# Stepper_driver_group.net
KiCad netlist of a schematic drawn in Altium Designer
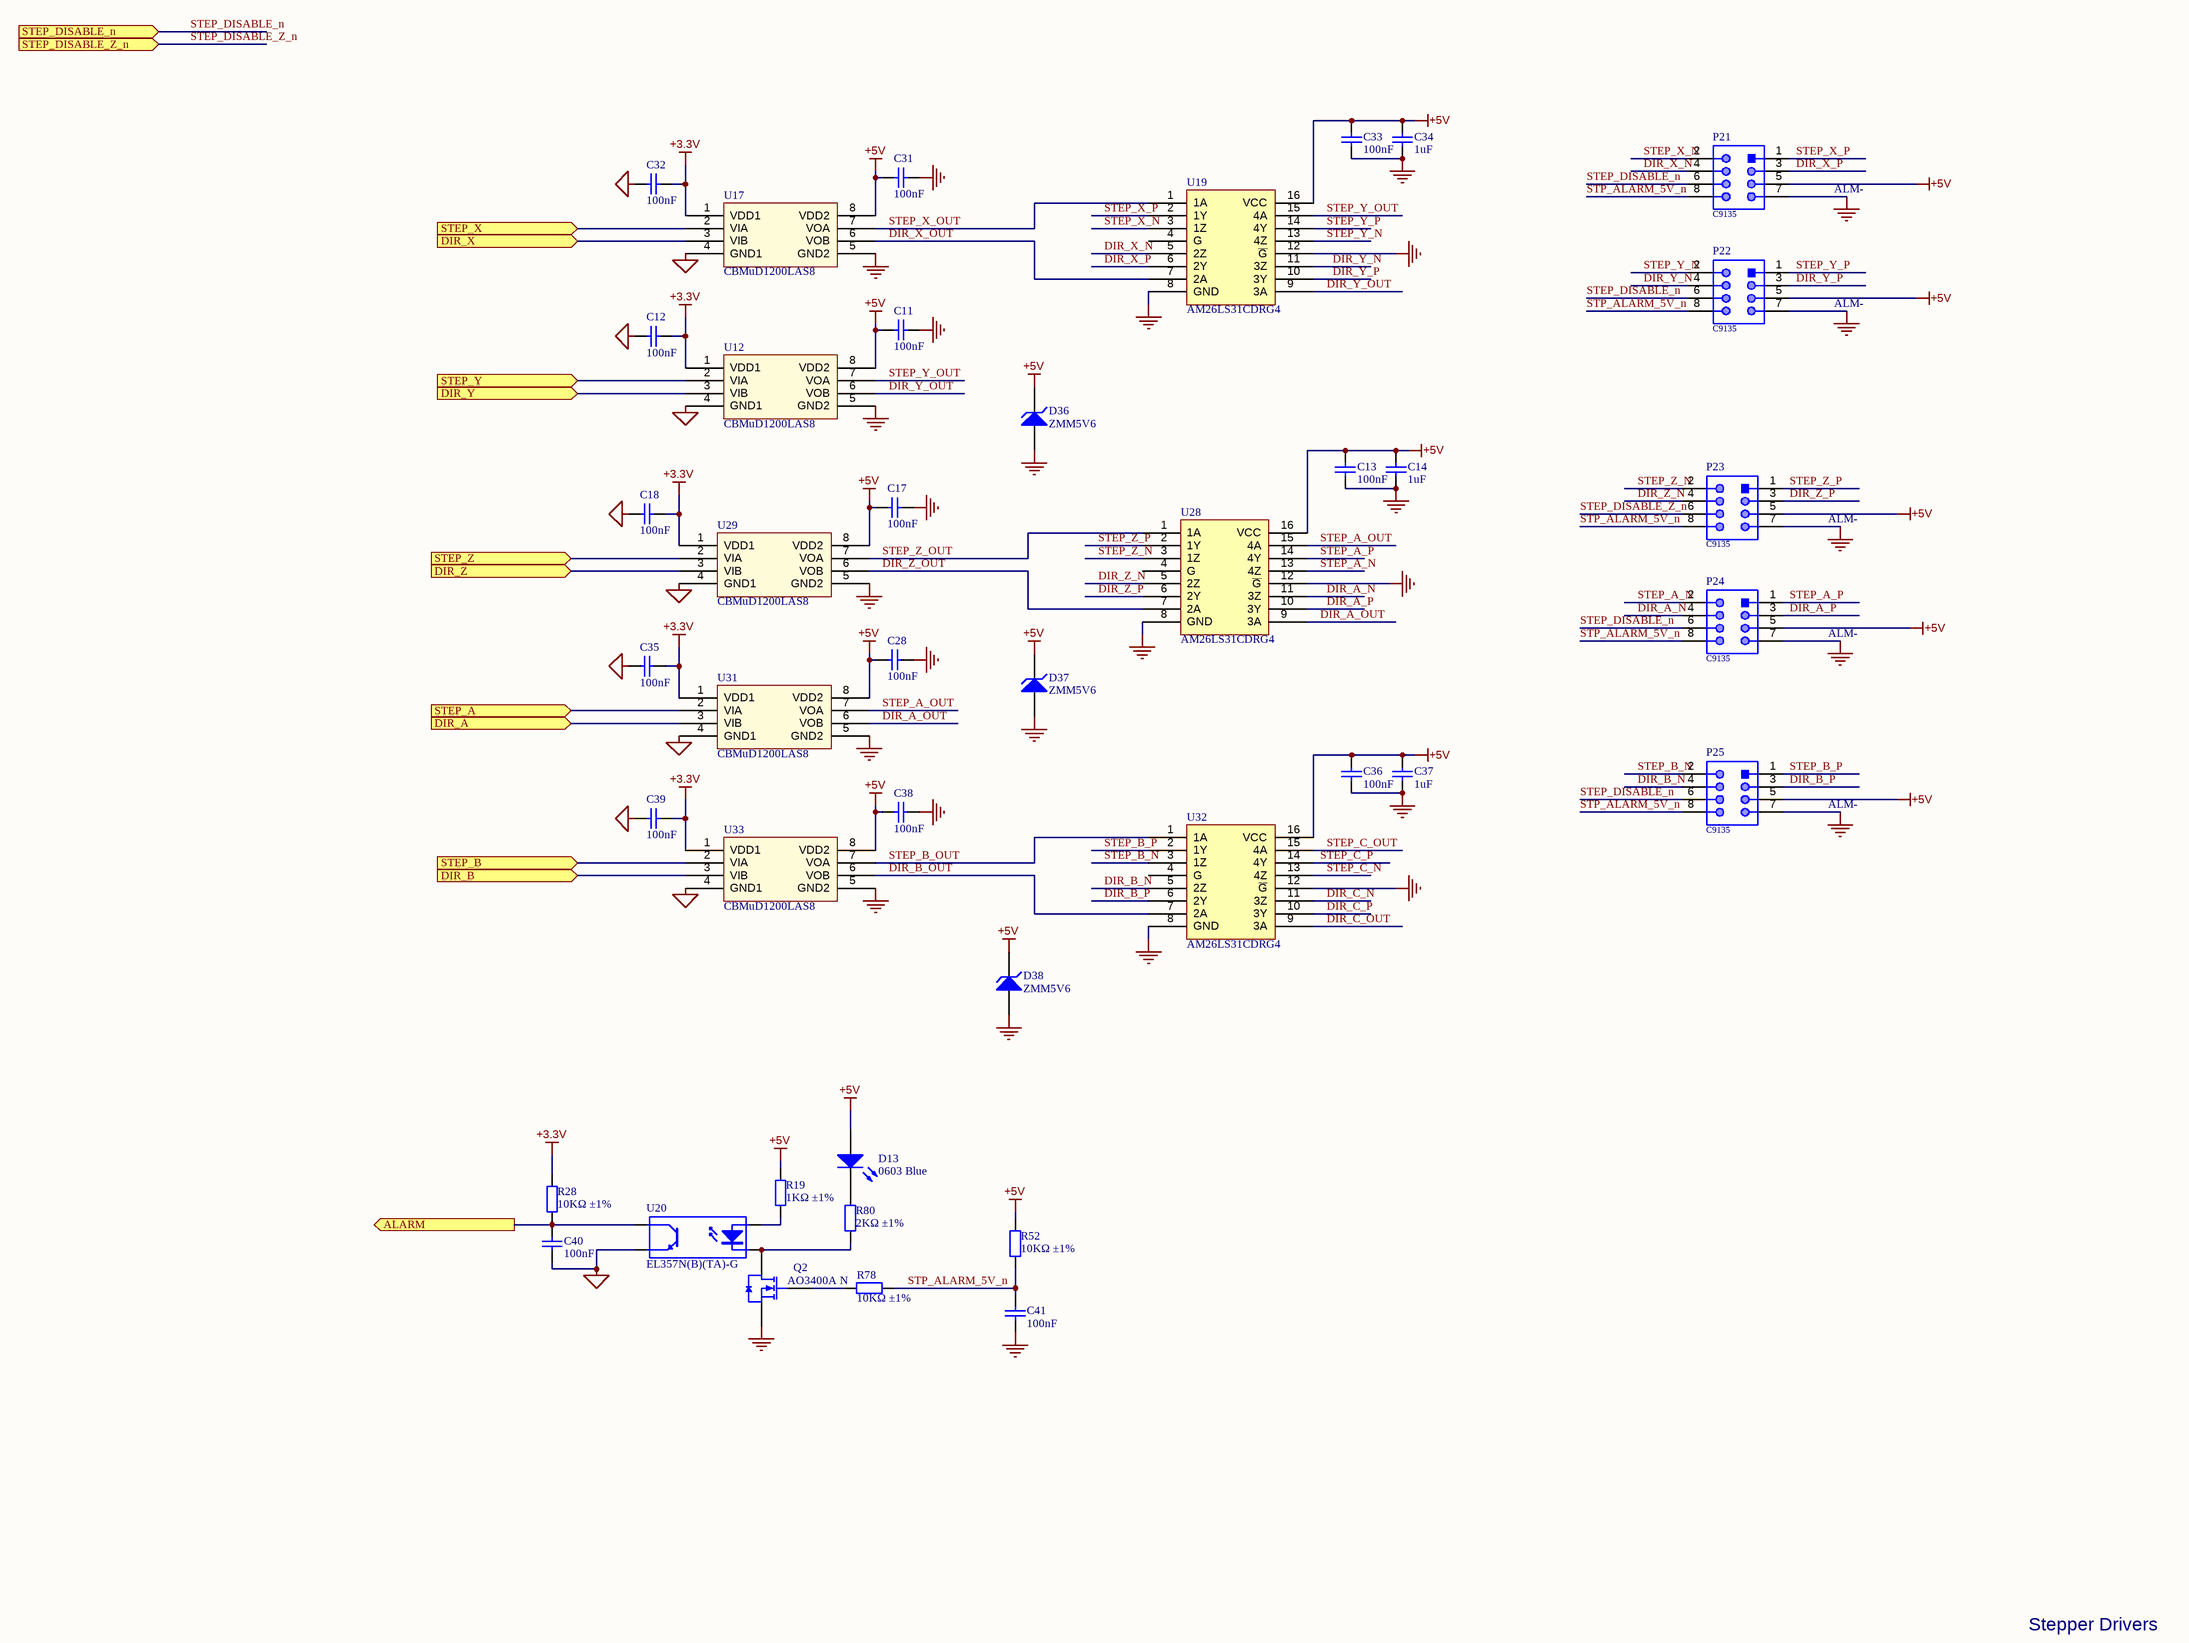
[diagram p0: Stepper_driver_group.SchDoc]

(export (version "E")
  (design (tool "Eeschema 10.0.6"))
  (components
    (comp (ref "C11")
      (value "100nF")
      (footprint "0603_C")
      (description "Chip capacitors")
      (fields (field (name "MANUFACTURER") "YAGEO") (field (name "PARTNUMBER") "CC0603KRX7R9BB104"))
      (libsource (lib "Cap") (part "0603 100nF (104) 10% 50V"))
    )
    (comp (ref "C12")
      (value "100nF")
      (footprint "0603_C")
      (description "Chip capacitors")
      (fields (field (name "MANUFACTURER") "YAGEO") (field (name "PARTNUMBER") "CC0603KRX7R9BB104"))
      (libsource (lib "Cap") (part "0603 100nF (104) 10% 50V"))
    )
    (comp (ref "C13")
      (value "100nF")
      (footprint "0603_C")
      (description "Chip capacitors")
      (fields (field (name "MANUFACTURER") "YAGEO") (field (name "PARTNUMBER") "CC0603KRX7R9BB104"))
      (libsource (lib "Cap") (part "0603 100nF (104) 10% 50V"))
    )
    (comp (ref "C14")
      (value "1uF")
      (footprint "0603_C")
      (description "Chip capacitors")
      (fields
        (field (name "MANUFACTURER") "Samsung Electro-Mechanics")
        (field (name "PARTNUMBER") "CL10A105KB8NNNC")
      )
      (libsource (lib "Cap") (part "0603 1uF (105) 10% 50V"))
    )
    (comp (ref "C17")
      (value "100nF")
      (footprint "0603_C")
      (description "Chip capacitors")
      (fields (field (name "MANUFACTURER") "YAGEO") (field (name "PARTNUMBER") "CC0603KRX7R9BB104"))
      (libsource (lib "Cap") (part "0603 100nF (104) 10% 50V"))
    )
    (comp (ref "C18")
      (value "100nF")
      (footprint "0603_C")
      (description "Chip capacitors")
      (fields (field (name "MANUFACTURER") "YAGEO") (field (name "PARTNUMBER") "CC0603KRX7R9BB104"))
      (libsource (lib "Cap") (part "0603 100nF (104) 10% 50V"))
    )
    (comp (ref "C28")
      (value "100nF")
      (footprint "0603_C")
      (description "Chip capacitors")
      (fields (field (name "MANUFACTURER") "YAGEO") (field (name "PARTNUMBER") "CC0603KRX7R9BB104"))
      (libsource (lib "Cap") (part "0603 100nF (104) 10% 50V"))
    )
    (comp (ref "C31")
      (value "100nF")
      (footprint "0603_C")
      (description "Chip capacitors")
      (fields (field (name "MANUFACTURER") "YAGEO") (field (name "PARTNUMBER") "CC0603KRX7R9BB104"))
      (libsource (lib "Cap") (part "0603 100nF (104) 10% 50V"))
    )
    (comp (ref "C32")
      (value "100nF")
      (footprint "0603_C")
      (description "Chip capacitors")
      (fields (field (name "MANUFACTURER") "YAGEO") (field (name "PARTNUMBER") "CC0603KRX7R9BB104"))
      (libsource (lib "Cap") (part "0603 100nF (104) 10% 50V"))
    )
    (comp (ref "C33")
      (value "100nF")
      (footprint "0603_C")
      (description "Chip capacitors")
      (fields (field (name "MANUFACTURER") "YAGEO") (field (name "PARTNUMBER") "CC0603KRX7R9BB104"))
      (libsource (lib "Cap") (part "0603 100nF (104) 10% 50V"))
    )
    (comp (ref "C34")
      (value "1uF")
      (footprint "0603_C")
      (description "Chip capacitors")
      (fields
        (field (name "MANUFACTURER") "Samsung Electro-Mechanics")
        (field (name "PARTNUMBER") "CL10A105KB8NNNC")
      )
      (libsource (lib "Cap") (part "0603 1uF (105) 10% 50V"))
    )
    (comp (ref "C35")
      (value "100nF")
      (footprint "0603_C")
      (description "Chip capacitors")
      (fields (field (name "MANUFACTURER") "YAGEO") (field (name "PARTNUMBER") "CC0603KRX7R9BB104"))
      (libsource (lib "Cap") (part "0603 100nF (104) 10% 50V"))
    )
    (comp (ref "C36")
      (value "100nF")
      (footprint "0603_C")
      (description "Chip capacitors")
      (fields (field (name "MANUFACTURER") "YAGEO") (field (name "PARTNUMBER") "CC0603KRX7R9BB104"))
      (libsource (lib "Cap") (part "0603 100nF (104) 10% 50V"))
    )
    (comp (ref "C37")
      (value "1uF")
      (footprint "0603_C")
      (description "Chip capacitors")
      (fields
        (field (name "MANUFACTURER") "Samsung Electro-Mechanics")
        (field (name "PARTNUMBER") "CL10A105KB8NNNC")
      )
      (libsource (lib "Cap") (part "0603 1uF (105) 10% 50V"))
    )
    (comp (ref "C38")
      (value "100nF")
      (footprint "0603_C")
      (description "Chip capacitors")
      (fields (field (name "MANUFACTURER") "YAGEO") (field (name "PARTNUMBER") "CC0603KRX7R9BB104"))
      (libsource (lib "Cap") (part "0603 100nF (104) 10% 50V"))
    )
    (comp (ref "C39")
      (value "100nF")
      (footprint "0603_C")
      (description "Chip capacitors")
      (fields (field (name "MANUFACTURER") "YAGEO") (field (name "PARTNUMBER") "CC0603KRX7R9BB104"))
      (libsource (lib "Cap") (part "0603 100nF (104) 10% 50V"))
    )
    (comp (ref "C40")
      (value "100nF")
      (footprint "0603_C")
      (description "Chip capacitors")
      (fields (field (name "MANUFACTURER") "YAGEO") (field (name "PARTNUMBER") "CC0603KRX7R9BB104"))
      (libsource (lib "Cap") (part "0603 100nF (104) 10% 50V"))
    )
    (comp (ref "C41")
      (value "100nF")
      (footprint "0603_C")
      (description "Chip capacitors")
      (fields (field (name "MANUFACTURER") "YAGEO") (field (name "PARTNUMBER") "CC0603KRX7R9BB104"))
      (libsource (lib "Cap") (part "0603 100nF (104) 10% 50V"))
    )
    (comp (ref "D13")
      (value "0603 Blue")
      (footprint "0603_LED_S1")
      (description "LED")
      (libsource (lib "LED") (part "0603 LED Blue"))
    )
    (comp (ref "D36")
      (value "ZMM5V6")
      (footprint "LL-34")
      (description "500mW - 0.1uA @ 1V 5.6V LL-34 Zener Diodes ROHS")
      (libsource (lib "Zener") (part "LL-34 ZMM5V6"))
    )
    (comp (ref "D37")
      (value "ZMM5V6")
      (footprint "LL-34")
      (description "500mW - 0.1uA @ 1V 5.6V LL-34 Zener Diodes ROHS")
      (libsource (lib "Zener") (part "LL-34 ZMM5V6"))
    )
    (comp (ref "D38")
      (value "ZMM5V6")
      (footprint "LL-34")
      (description "500mW - 0.1uA @ 1V 5.6V LL-34 Zener Diodes ROHS")
      (libsource (lib "Zener") (part "LL-34 ZMM5V6"))
    )
    (comp (ref "P21")
      (value "C9135")
      (footprint "61200821621")
      (description "Male Box Header WR-BHD, THT, Vertical, pitch 2.54 mm, 8 pins")
      (fields (field (name "MANUFACTURER") "Wurth Elektronik") (field (name "PUBLISHER") "WurthElektronik"))
      (libsource (lib "PrintNC_GRBLHAL_Breakout") (part "WE-CN-2P-M-R8"))
    )
    (comp (ref "P22")
      (value "C9135")
      (footprint "61200821621")
      (description "Male Box Header WR-BHD, THT, Vertical, pitch 2.54 mm, 8 pins")
      (fields (field (name "MANUFACTURER") "Wurth Elektronik") (field (name "PUBLISHER") "WurthElektronik"))
      (libsource (lib "PrintNC_GRBLHAL_Breakout") (part "WE-CN-2P-M-R8"))
    )
    (comp (ref "P23")
      (value "C9135")
      (footprint "61200821621")
      (description "Male Box Header WR-BHD, THT, Vertical, pitch 2.54 mm, 8 pins")
      (fields (field (name "MANUFACTURER") "Wurth Elektronik") (field (name "PUBLISHER") "WurthElektronik"))
      (libsource (lib "PrintNC_GRBLHAL_Breakout") (part "WE-CN-2P-M-R8"))
    )
    (comp (ref "P24")
      (value "C9135")
      (footprint "61200821621")
      (description "Male Box Header WR-BHD, THT, Vertical, pitch 2.54 mm, 8 pins")
      (fields (field (name "MANUFACTURER") "Wurth Elektronik") (field (name "PUBLISHER") "WurthElektronik"))
      (libsource (lib "PrintNC_GRBLHAL_Breakout") (part "WE-CN-2P-M-R8"))
    )
    (comp (ref "P25")
      (value "C9135")
      (footprint "61200821621")
      (description "Male Box Header WR-BHD, THT, Vertical, pitch 2.54 mm, 8 pins")
      (fields (field (name "MANUFACTURER") "Wurth Elektronik") (field (name "PUBLISHER") "WurthElektronik"))
      (libsource (lib "PrintNC_GRBLHAL_Breakout") (part "WE-CN-2P-M-R8"))
    )
    (comp (ref "Q2")
      (value "AO3400A N")
      (footprint "SOT-23-3L")
      (description "MOS(场效应管)")
      (libsource (lib "MOS") (part "AO3400A N道沟 X0YV1T SOT-23"))
    )
    (comp (ref "R19")
      (value "1KΩ ±1%")
      (footprint "0603_R")
      (description "Chip resistor")
      (fields (field (name "MANUFACTURER") "Uniroyal Elec") (field (name "PARTNUMBER") "0603WAF1001T5E"))
      (libsource (lib "RES") (part "0603 1K (1001) 1%"))
    )
    (comp (ref "R28")
      (value "10KΩ ±1%")
      (footprint "0603_R")
      (description "Chip resistor")
      (fields (field (name "MANUFACTURER") "Uniroyal Elec") (field (name "PARTNUMBER") "0603WAF1002T5E"))
      (libsource (lib "") (part "0603 10K (1002) 1%_1"))
    )
    (comp (ref "R52")
      (value "10KΩ ±1%")
      (footprint "0603_R")
      (description "Chip resistor")
      (fields (field (name "MANUFACTURER") "Uniroyal Elec") (field (name "PARTNUMBER") "0603WAF1002T5E"))
      (libsource (lib "") (part "0603 10K (1002) 1%_2"))
    )
    (comp (ref "R78")
      (value "10KΩ ±1%")
      (footprint "0603_R")
      (description "Chip resistor")
      (fields (field (name "MANUFACTURER") "Uniroyal Elec") (field (name "PARTNUMBER") "0603WAF1002T5E"))
      (libsource (lib "RES") (part "0603 10K (1002) 1%"))
    )
    (comp (ref "R80")
      (value "2KΩ ±1%")
      (footprint "0603_R")
      (description "Chip resistor")
      (fields (field (name "MANUFACTURER") "Uniroyal Elec") (field (name "PARTNUMBER") "0603WAF2001T5E"))
      (libsource (lib "RES") (part "0603 2K (2001) 1%"))
    )
    (comp (ref "U12")
      (value "CBMuD1200LAS8")
      (footprint "SOIC-8_150mil")
      (description "Dual Channel Isolator")
      (libsource (lib "IC") (part "CBMuD1200LAS8"))
    )
    (comp (ref "U17")
      (value "CBMuD1200LAS8")
      (footprint "SOIC-8_150mil")
      (description "Dual Channel Isolator")
      (libsource (lib "IC") (part "CBMuD1200LAS8"))
    )
    (comp (ref "U19")
      (value "AM26LS31CDRG4")
      (footprint "SOIC-16_150mil")
      (description "4/0 Driver - RS422, RS485 16-SOIC")
      (libsource (lib "IC") (part "AM26LS31CDRG4_[C6179]"))
    )
    (comp (ref "U20")
      (value "EL357N(B)(TA)-G")
      (footprint "SOP-4_P2.54")
      (description "OPTOISOLATOR 3.75KV TRANS 4-SOP")
      (libsource (lib "PrintNC_GRBLHAL_Breakout") (part "EL357N(B)(TA)-G_[C6649]"))
    )
    (comp (ref "U28")
      (value "AM26LS31CDRG4")
      (footprint "SOIC-16_150mil")
      (description "4/0 Driver - RS422, RS485 16-SOIC")
      (libsource (lib "IC") (part "AM26LS31CDRG4_[C6179]"))
    )
    (comp (ref "U29")
      (value "CBMuD1200LAS8")
      (footprint "SOIC-8_150mil")
      (description "Dual Channel Isolator")
      (libsource (lib "IC") (part "CBMuD1200LAS8"))
    )
    (comp (ref "U31")
      (value "CBMuD1200LAS8")
      (footprint "SOIC-8_150mil")
      (description "Dual Channel Isolator")
      (libsource (lib "IC") (part "CBMuD1200LAS8"))
    )
    (comp (ref "U32")
      (value "AM26LS31CDRG4")
      (footprint "SOIC-16_150mil")
      (description "4/0 Driver - RS422, RS485 16-SOIC")
      (libsource (lib "IC") (part "AM26LS31CDRG4_[C6179]"))
    )
    (comp (ref "U33")
      (value "CBMuD1200LAS8")
      (footprint "SOIC-8_150mil")
      (description "Dual Channel Isolator")
      (libsource (lib "IC") (part "CBMuD1200LAS8"))
    )
  )
  (nets
    (net (code "1") (name "+3.3V") (class "Default")
      (node (ref "C12") (pin "1") (pinfunction "1_1") (pintype "passive"))
      (node (ref "C18") (pin "1") (pinfunction "1_1") (pintype "passive"))
      (node (ref "C32") (pin "1") (pinfunction "1_1") (pintype "passive"))
      (node (ref "C35") (pin "1") (pinfunction "1_1") (pintype "passive"))
      (node (ref "C39") (pin "1") (pinfunction "1_1") (pintype "passive"))
      (node (ref "R28") (pin "2") (pinfunction "2_2") (pintype "passive"))
      (node (ref "U12") (pin "1") (pinfunction "VDD1_1") (pintype "passive"))
      (node (ref "U17") (pin "1") (pinfunction "VDD1_1") (pintype "passive"))
      (node (ref "U29") (pin "1") (pinfunction "VDD1_1") (pintype "passive"))
      (node (ref "U31") (pin "1") (pinfunction "VDD1_1") (pintype "passive"))
      (node (ref "U33") (pin "1") (pinfunction "VDD1_1") (pintype "passive"))
    )
    (net (code "2") (name "+5V") (class "Default")
      (node (ref "C11") (pin "2") (pinfunction "2_2") (pintype "passive"))
      (node (ref "C13") (pin "1") (pinfunction "1_1") (pintype "passive"))
      (node (ref "C14") (pin "1") (pinfunction "1_1") (pintype "passive"))
      (node (ref "C17") (pin "2") (pinfunction "2_2") (pintype "passive"))
      (node (ref "C28") (pin "2") (pinfunction "2_2") (pintype "passive"))
      (node (ref "C31") (pin "2") (pinfunction "2_2") (pintype "passive"))
      (node (ref "C33") (pin "1") (pinfunction "1_1") (pintype "passive"))
      (node (ref "C34") (pin "1") (pinfunction "1_1") (pintype "passive"))
      (node (ref "C36") (pin "1") (pinfunction "1_1") (pintype "passive"))
      (node (ref "C37") (pin "1") (pinfunction "1_1") (pintype "passive"))
      (node (ref "C38") (pin "2") (pinfunction "2_2") (pintype "passive"))
      (node (ref "D13") (pin "A") (pinfunction "A_A") (pintype "passive"))
      (node (ref "D36") (pin "2") (pinfunction "K_2") (pintype "passive"))
      (node (ref "D37") (pin "2") (pinfunction "K_2") (pintype "passive"))
      (node (ref "D38") (pin "2") (pinfunction "K_2") (pintype "passive"))
      (node (ref "P21") (pin "5") (pinfunction "5_5") (pintype "passive"))
      (node (ref "P22") (pin "5") (pinfunction "5_5") (pintype "passive"))
      (node (ref "P23") (pin "5") (pinfunction "5_5") (pintype "passive"))
      (node (ref "P24") (pin "5") (pinfunction "5_5") (pintype "passive"))
      (node (ref "P25") (pin "5") (pinfunction "5_5") (pintype "passive"))
      (node (ref "R19") (pin "1") (pinfunction "1_1") (pintype "passive"))
      (node (ref "R52") (pin "2") (pinfunction "2_2") (pintype "passive"))
      (node (ref "U12") (pin "8") (pinfunction "VDD2_8") (pintype "passive"))
      (node (ref "U17") (pin "8") (pinfunction "VDD2_8") (pintype "passive"))
      (node (ref "U19") (pin "16") (pinfunction "VCC_16") (pintype "passive"))
      (node (ref "U28") (pin "16") (pinfunction "VCC_16") (pintype "passive"))
      (node (ref "U29") (pin "8") (pinfunction "VDD2_8") (pintype "passive"))
      (node (ref "U31") (pin "8") (pinfunction "VDD2_8") (pintype "passive"))
      (node (ref "U32") (pin "16") (pinfunction "VCC_16") (pintype "passive"))
      (node (ref "U33") (pin "8") (pinfunction "VDD2_8") (pintype "passive"))
    )
    (net (code "3") (name "/ALARM") (class "Default")
      (node (ref "C40") (pin "2") (pinfunction "2_2") (pintype "passive"))
      (node (ref "R28") (pin "1") (pinfunction "1_1") (pintype "passive"))
      (node (ref "U20") (pin "4") (pinfunction "C_4") (pintype "passive"))
    )
    (net (code "4") (name "/DIR_A") (class "Default")
      (node (ref "U31") (pin "3") (pinfunction "VIB_3") (pintype "passive"))
    )
    (net (code "5") (name "/DIR_A_N") (class "Default")
      (node (ref "P24") (pin "4") (pinfunction "4_4") (pintype "passive"))
      (node (ref "U28") (pin "11") (pinfunction "3Z_11") (pintype "passive"))
    )
    (net (code "6") (name "/DIR_A_OUT") (class "Default")
      (node (ref "U28") (pin "9") (pinfunction "3A_9") (pintype "passive"))
      (node (ref "U31") (pin "6") (pinfunction "VOB_6") (pintype "passive"))
    )
    (net (code "7") (name "/DIR_A_P") (class "Default")
      (node (ref "P24") (pin "3") (pinfunction "3_3") (pintype "passive"))
      (node (ref "U28") (pin "10") (pinfunction "3Y_10") (pintype "passive"))
    )
    (net (code "8") (name "/DIR_B") (class "Default")
      (node (ref "U33") (pin "3") (pinfunction "VIB_3") (pintype "passive"))
    )
    (net (code "9") (name "/DIR_B_N") (class "Default")
      (node (ref "P25") (pin "4") (pinfunction "4_4") (pintype "passive"))
      (node (ref "U32") (pin "5") (pinfunction "2Z_5") (pintype "passive"))
    )
    (net (code "10") (name "/DIR_B_OUT") (class "Default")
      (node (ref "U32") (pin "7") (pinfunction "2A_7") (pintype "passive"))
      (node (ref "U33") (pin "6") (pinfunction "VOB_6") (pintype "passive"))
    )
    (net (code "11") (name "/DIR_B_P") (class "Default")
      (node (ref "P25") (pin "3") (pinfunction "3_3") (pintype "passive"))
      (node (ref "U32") (pin "6") (pinfunction "2Y_6") (pintype "passive"))
    )
    (net (code "12") (name "/DIR_C_N") (class "Default")
      (node (ref "U32") (pin "11") (pinfunction "3Z_11") (pintype "passive"))
    )
    (net (code "13") (name "/DIR_C_OUT") (class "Default")
      (node (ref "U32") (pin "9") (pinfunction "3A_9") (pintype "passive"))
    )
    (net (code "14") (name "/DIR_C_P") (class "Default")
      (node (ref "U32") (pin "10") (pinfunction "3Y_10") (pintype "passive"))
    )
    (net (code "15") (name "/DIR_X") (class "Default")
      (node (ref "U17") (pin "3") (pinfunction "VIB_3") (pintype "passive"))
    )
    (net (code "16") (name "/DIR_X_N") (class "Default")
      (node (ref "P21") (pin "4") (pinfunction "4_4") (pintype "passive"))
      (node (ref "U19") (pin "5") (pinfunction "2Z_5") (pintype "passive"))
    )
    (net (code "17") (name "/DIR_X_OUT") (class "Default")
      (node (ref "U17") (pin "6") (pinfunction "VOB_6") (pintype "passive"))
      (node (ref "U19") (pin "7") (pinfunction "2A_7") (pintype "passive"))
    )
    (net (code "18") (name "/DIR_X_P") (class "Default")
      (node (ref "P21") (pin "3") (pinfunction "3_3") (pintype "passive"))
      (node (ref "U19") (pin "6") (pinfunction "2Y_6") (pintype "passive"))
    )
    (net (code "19") (name "/DIR_Y") (class "Default")
      (node (ref "U12") (pin "3") (pinfunction "VIB_3") (pintype "passive"))
    )
    (net (code "20") (name "/DIR_Y_N") (class "Default")
      (node (ref "P22") (pin "4") (pinfunction "4_4") (pintype "passive"))
      (node (ref "U19") (pin "11") (pinfunction "3Z_11") (pintype "passive"))
    )
    (net (code "21") (name "/DIR_Y_OUT") (class "Default")
      (node (ref "U12") (pin "6") (pinfunction "VOB_6") (pintype "passive"))
      (node (ref "U19") (pin "9") (pinfunction "3A_9") (pintype "passive"))
    )
    (net (code "22") (name "/DIR_Y_P") (class "Default")
      (node (ref "P22") (pin "3") (pinfunction "3_3") (pintype "passive"))
      (node (ref "U19") (pin "10") (pinfunction "3Y_10") (pintype "passive"))
    )
    (net (code "23") (name "/DIR_Z") (class "Default")
      (node (ref "U29") (pin "3") (pinfunction "VIB_3") (pintype "passive"))
    )
    (net (code "24") (name "/DIR_Z_N") (class "Default")
      (node (ref "P23") (pin "4") (pinfunction "4_4") (pintype "passive"))
      (node (ref "U28") (pin "5") (pinfunction "2Z_5") (pintype "passive"))
    )
    (net (code "25") (name "/DIR_Z_OUT") (class "Default")
      (node (ref "U28") (pin "7") (pinfunction "2A_7") (pintype "passive"))
      (node (ref "U29") (pin "6") (pinfunction "VOB_6") (pintype "passive"))
    )
    (net (code "26") (name "/DIR_Z_P") (class "Default")
      (node (ref "P23") (pin "3") (pinfunction "3_3") (pintype "passive"))
      (node (ref "U28") (pin "6") (pinfunction "2Y_6") (pintype "passive"))
    )
    (net (code "27") (name "/STEP_A") (class "Default")
      (node (ref "U31") (pin "2") (pinfunction "VIA_2") (pintype "passive"))
    )
    (net (code "28") (name "/STEP_A_N") (class "Default")
      (node (ref "P24") (pin "2") (pinfunction "2_2") (pintype "passive"))
      (node (ref "U28") (pin "13") (pinfunction "4Z_13") (pintype "passive"))
    )
    (net (code "29") (name "/STEP_A_OUT") (class "Default")
      (node (ref "U28") (pin "15") (pinfunction "4A_15") (pintype "passive"))
      (node (ref "U31") (pin "7") (pinfunction "VOA_7") (pintype "passive"))
    )
    (net (code "30") (name "/STEP_A_P") (class "Default")
      (node (ref "P24") (pin "1") (pinfunction "1_1") (pintype "passive"))
      (node (ref "U28") (pin "14") (pinfunction "4Y_14") (pintype "passive"))
    )
    (net (code "31") (name "/STEP_B") (class "Default")
      (node (ref "U33") (pin "2") (pinfunction "VIA_2") (pintype "passive"))
    )
    (net (code "32") (name "/STEP_B_N") (class "Default")
      (node (ref "P25") (pin "2") (pinfunction "2_2") (pintype "passive"))
      (node (ref "U32") (pin "3") (pinfunction "1Z_3") (pintype "passive"))
    )
    (net (code "33") (name "/STEP_B_OUT") (class "Default")
      (node (ref "U32") (pin "1") (pinfunction "1A_1") (pintype "passive"))
      (node (ref "U33") (pin "7") (pinfunction "VOA_7") (pintype "passive"))
    )
    (net (code "34") (name "/STEP_B_P") (class "Default")
      (node (ref "P25") (pin "1") (pinfunction "1_1") (pintype "passive"))
      (node (ref "U32") (pin "2") (pinfunction "1Y_2") (pintype "passive"))
    )
    (net (code "35") (name "/STEP_C_N") (class "Default")
      (node (ref "U32") (pin "13") (pinfunction "4Z_13") (pintype "passive"))
    )
    (net (code "36") (name "/STEP_C_OUT") (class "Default")
      (node (ref "U32") (pin "15") (pinfunction "4A_15") (pintype "passive"))
    )
    (net (code "37") (name "/STEP_C_P") (class "Default")
      (node (ref "U32") (pin "14") (pinfunction "4Y_14") (pintype "passive"))
    )
    (net (code "38") (name "/STEP_DISABLE_Z_n") (class "Default")
      (node (ref "P23") (pin "6") (pinfunction "6_6") (pintype "passive"))
    )
    (net (code "39") (name "/STEP_DISABLE_n") (class "Default")
      (node (ref "P21") (pin "6") (pinfunction "6_6") (pintype "passive"))
      (node (ref "P22") (pin "6") (pinfunction "6_6") (pintype "passive"))
      (node (ref "P24") (pin "6") (pinfunction "6_6") (pintype "passive"))
      (node (ref "P25") (pin "6") (pinfunction "6_6") (pintype "passive"))
    )
    (net (code "40") (name "/STEP_X") (class "Default")
      (node (ref "U17") (pin "2") (pinfunction "VIA_2") (pintype "passive"))
    )
    (net (code "41") (name "/STEP_X_N") (class "Default")
      (node (ref "P21") (pin "2") (pinfunction "2_2") (pintype "passive"))
      (node (ref "U19") (pin "3") (pinfunction "1Z_3") (pintype "passive"))
    )
    (net (code "42") (name "/STEP_X_OUT") (class "Default")
      (node (ref "U17") (pin "7") (pinfunction "VOA_7") (pintype "passive"))
      (node (ref "U19") (pin "1") (pinfunction "1A_1") (pintype "passive"))
    )
    (net (code "43") (name "/STEP_X_P") (class "Default")
      (node (ref "P21") (pin "1") (pinfunction "1_1") (pintype "passive"))
      (node (ref "U19") (pin "2") (pinfunction "1Y_2") (pintype "passive"))
    )
    (net (code "44") (name "/STEP_Y") (class "Default")
      (node (ref "U12") (pin "2") (pinfunction "VIA_2") (pintype "passive"))
    )
    (net (code "45") (name "/STEP_Y_N") (class "Default")
      (node (ref "P22") (pin "2") (pinfunction "2_2") (pintype "passive"))
      (node (ref "U19") (pin "13") (pinfunction "4Z_13") (pintype "passive"))
    )
    (net (code "46") (name "/STEP_Y_OUT") (class "Default")
      (node (ref "U12") (pin "7") (pinfunction "VOA_7") (pintype "passive"))
      (node (ref "U19") (pin "15") (pinfunction "4A_15") (pintype "passive"))
    )
    (net (code "47") (name "/STEP_Y_P") (class "Default")
      (node (ref "P22") (pin "1") (pinfunction "1_1") (pintype "passive"))
      (node (ref "U19") (pin "14") (pinfunction "4Y_14") (pintype "passive"))
    )
    (net (code "48") (name "/STEP_Z") (class "Default")
      (node (ref "U29") (pin "2") (pinfunction "VIA_2") (pintype "passive"))
    )
    (net (code "49") (name "/STEP_Z_N") (class "Default")
      (node (ref "P23") (pin "2") (pinfunction "2_2") (pintype "passive"))
      (node (ref "U28") (pin "3") (pinfunction "1Z_3") (pintype "passive"))
    )
    (net (code "50") (name "/STEP_Z_OUT") (class "Default")
      (node (ref "U28") (pin "1") (pinfunction "1A_1") (pintype "passive"))
      (node (ref "U29") (pin "7") (pinfunction "VOA_7") (pintype "passive"))
    )
    (net (code "51") (name "/STEP_Z_P") (class "Default")
      (node (ref "P23") (pin "1") (pinfunction "1_1") (pintype "passive"))
      (node (ref "U28") (pin "2") (pinfunction "1Y_2") (pintype "passive"))
    )
    (net (code "52") (name "/STP_ALARM_5V_n") (class "Default")
      (node (ref "C41") (pin "2") (pinfunction "2_2") (pintype "passive"))
      (node (ref "P21") (pin "8") (pinfunction "8_8") (pintype "passive"))
      (node (ref "P22") (pin "8") (pinfunction "8_8") (pintype "passive"))
      (node (ref "P23") (pin "8") (pinfunction "8_8") (pintype "passive"))
      (node (ref "P24") (pin "8") (pinfunction "8_8") (pintype "passive"))
      (node (ref "P25") (pin "8") (pinfunction "8_8") (pintype "passive"))
      (node (ref "R52") (pin "1") (pinfunction "1_1") (pintype "passive"))
      (node (ref "R78") (pin "1") (pinfunction "1_1") (pintype "passive"))
    )
    (net (code "53") (name "GND") (class "Default")
      (node (ref "C11") (pin "1") (pinfunction "1_1") (pintype "passive"))
      (node (ref "C13") (pin "2") (pinfunction "2_2") (pintype "passive"))
      (node (ref "C14") (pin "2") (pinfunction "2_2") (pintype "passive"))
      (node (ref "C17") (pin "1") (pinfunction "1_1") (pintype "passive"))
      (node (ref "C28") (pin "1") (pinfunction "1_1") (pintype "passive"))
      (node (ref "C31") (pin "1") (pinfunction "1_1") (pintype "passive"))
      (node (ref "C33") (pin "2") (pinfunction "2_2") (pintype "passive"))
      (node (ref "C34") (pin "2") (pinfunction "2_2") (pintype "passive"))
      (node (ref "C36") (pin "2") (pinfunction "2_2") (pintype "passive"))
      (node (ref "C37") (pin "2") (pinfunction "2_2") (pintype "passive"))
      (node (ref "C38") (pin "1") (pinfunction "1_1") (pintype "passive"))
      (node (ref "C41") (pin "1") (pinfunction "1_1") (pintype "passive"))
      (node (ref "D36") (pin "1") (pinfunction "A_1") (pintype "passive"))
      (node (ref "D37") (pin "1") (pinfunction "A_1") (pintype "passive"))
      (node (ref "D38") (pin "1") (pinfunction "A_1") (pintype "passive"))
      (node (ref "P21") (pin "7") (pinfunction "7_7") (pintype "passive"))
      (node (ref "P22") (pin "7") (pinfunction "7_7") (pintype "passive"))
      (node (ref "P23") (pin "7") (pinfunction "7_7") (pintype "passive"))
      (node (ref "P24") (pin "7") (pinfunction "7_7") (pintype "passive"))
      (node (ref "P25") (pin "7") (pinfunction "7_7") (pintype "passive"))
      (node (ref "Q2") (pin "2") (pinfunction "S_2") (pintype "passive"))
      (node (ref "U12") (pin "5") (pinfunction "GND2_5") (pintype "passive"))
      (node (ref "U17") (pin "5") (pinfunction "GND2_5") (pintype "passive"))
      (node (ref "U19") (pin "12") (pinfunction "~{G}_12") (pintype "passive"))
      (node (ref "U19") (pin "8") (pinfunction "GND_8") (pintype "passive"))
      (node (ref "U28") (pin "12") (pinfunction "~{G}_12") (pintype "passive"))
      (node (ref "U28") (pin "8") (pinfunction "GND_8") (pintype "passive"))
      (node (ref "U29") (pin "5") (pinfunction "GND2_5") (pintype "passive"))
      (node (ref "U31") (pin "5") (pinfunction "GND2_5") (pintype "passive"))
      (node (ref "U32") (pin "12") (pinfunction "~{G}_12") (pintype "passive"))
      (node (ref "U32") (pin "8") (pinfunction "GND_8") (pintype "passive"))
      (node (ref "U33") (pin "5") (pinfunction "GND2_5") (pintype "passive"))
    )
    (net (code "54") (name "MCU_GND") (class "Default")
      (node (ref "C12") (pin "2") (pinfunction "2_2") (pintype "passive"))
      (node (ref "C18") (pin "2") (pinfunction "2_2") (pintype "passive"))
      (node (ref "C32") (pin "2") (pinfunction "2_2") (pintype "passive"))
      (node (ref "C35") (pin "2") (pinfunction "2_2") (pintype "passive"))
      (node (ref "C39") (pin "2") (pinfunction "2_2") (pintype "passive"))
      (node (ref "C40") (pin "1") (pinfunction "1_1") (pintype "passive"))
      (node (ref "U12") (pin "4") (pinfunction "GND1_4") (pintype "passive"))
      (node (ref "U17") (pin "4") (pinfunction "GND1_4") (pintype "passive"))
      (node (ref "U20") (pin "3") (pinfunction "E_3") (pintype "passive"))
      (node (ref "U29") (pin "4") (pinfunction "GND1_4") (pintype "passive"))
      (node (ref "U31") (pin "4") (pinfunction "GND1_4") (pintype "passive"))
      (node (ref "U33") (pin "4") (pinfunction "GND1_4") (pintype "passive"))
    )
    (net (code "55") (name "Net-(D13-PadK)") (class "Default")
      (node (ref "D13") (pin "K") (pinfunction "K_K") (pintype "passive"))
      (node (ref "R80") (pin "2") (pinfunction "2_2") (pintype "passive"))
    )
    (net (code "56") (name "Net-(Q2-D)") (class "Default")
      (node (ref "Q2") (pin "3") (pinfunction "D_3") (pintype "passive"))
      (node (ref "R80") (pin "1") (pinfunction "1_1") (pintype "passive"))
      (node (ref "U20") (pin "2") (pinfunction "K_2") (pintype "passive"))
    )
    (net (code "57") (name "Net-(Q2-G)") (class "Default")
      (node (ref "Q2") (pin "1") (pinfunction "G_1") (pintype "passive"))
      (node (ref "R78") (pin "2") (pinfunction "2_2") (pintype "passive"))
    )
    (net (code "58") (name "Net-(U20-A)") (class "Default")
      (node (ref "R19") (pin "2") (pinfunction "2_2") (pintype "passive"))
      (node (ref "U20") (pin "1") (pinfunction "A_1") (pintype "passive"))
    )
    (net (code "59") (name "unconnected-(U19-G-Pad4)") (class "Default")
      (node (ref "U19") (pin "4") (pinfunction "G_4") (pintype "passive"))
    )
    (net (code "60") (name "unconnected-(U28-G-Pad4)") (class "Default")
      (node (ref "U28") (pin "4") (pinfunction "G_4") (pintype "passive"))
    )
    (net (code "61") (name "unconnected-(U32-G-Pad4)") (class "Default")
      (node (ref "U32") (pin "4") (pinfunction "G_4") (pintype "passive"))
    )
  )
)
